# Teensy32.net
KiCad netlist of a schematic drawn in Altium Designer
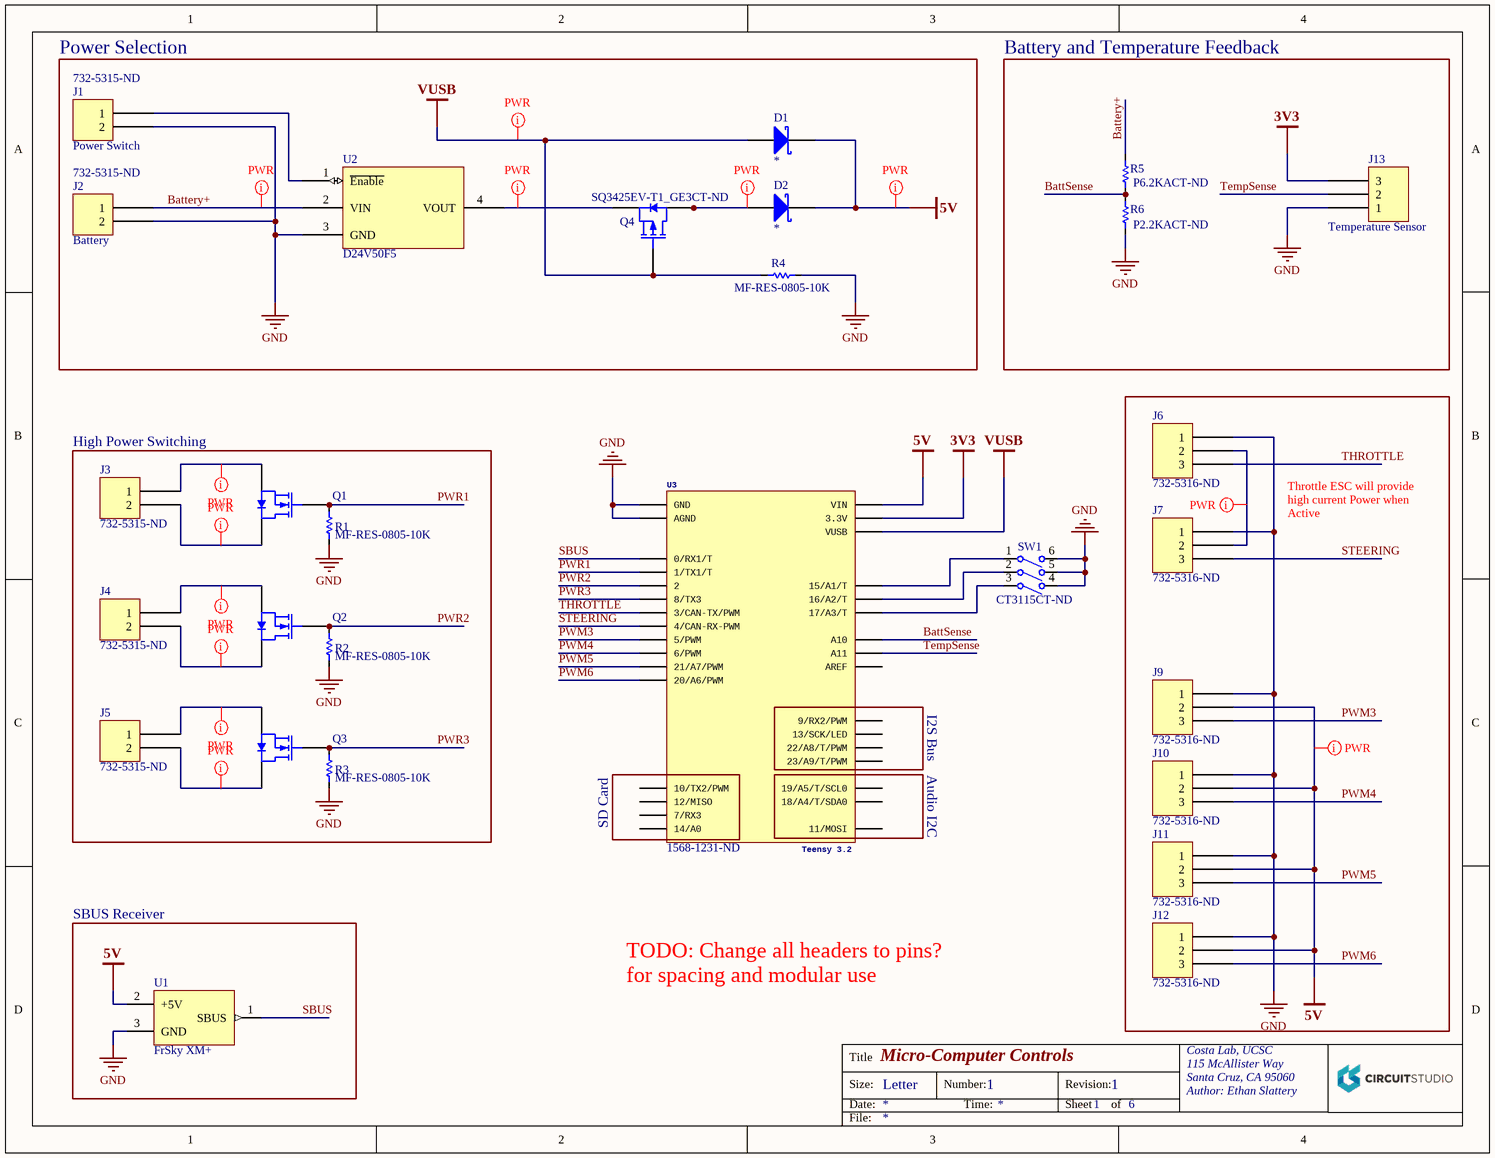
[diagram p0: Teensy32.SchDoc]

(export (version "E")
  (design (tool "Eeschema 10.0.6"))
  (components
    (comp (ref "D1") (value "*") (libsource (lib "DiscreetSemiconductors") (part "Schottky Diode")))
    (comp (ref "D2") (value "*") (libsource (lib "DiscreetSemiconductors") (part "Schottky Diode")))
    (comp (ref "J1")
      (value "Power Switch")
      (footprint "Pinhead_1x2")
      (fields (field (name "SUPPLIER PART NUMBER 1") "732-5315-ND"))
      (libsource (lib "Connectors") (part "2 Pin"))
    )
    (comp (ref "J2")
      (value "Battery")
      (footprint "Pinhead_1x2")
      (fields (field (name "SUPPLIER PART NUMBER 1") "732-5315-ND"))
      (libsource (lib "Connectors") (part "2 Pin"))
    )
    (comp (ref "J3")
      (value "732-5315-ND")
      (footprint "Pinhead_1x2")
      (libsource (lib "Connectors") (part "2 Pin"))
    )
    (comp (ref "J4")
      (value "732-5315-ND")
      (footprint "Pinhead_1x2")
      (libsource (lib "Connectors") (part "2 Pin"))
    )
    (comp (ref "J5")
      (value "732-5315-ND")
      (footprint "Pinhead_1x2")
      (libsource (lib "Connectors") (part "2 Pin"))
    )
    (comp (ref "J6")
      (value "Header")
      (footprint "Pinhead_1x3")
      (fields (field (name "SUPPLIER PART NUMBER 1") "732-5316-ND"))
      (libsource (lib "Connectors") (part "3 Pin"))
    )
    (comp (ref "J7")
      (value "Header")
      (footprint "Pinhead_1x3")
      (fields (field (name "SUPPLIER PART NUMBER 1") "732-5316-ND"))
      (libsource (lib "Connectors") (part "3 Pin"))
    )
    (comp (ref "J9")
      (value "Header")
      (footprint "Pinhead_1x3")
      (fields (field (name "SUPPLIER PART NUMBER 1") "732-5316-ND"))
      (libsource (lib "Connectors") (part "3 Pin"))
    )
    (comp (ref "J10")
      (value "Header")
      (footprint "Pinhead_1x3")
      (fields (field (name "SUPPLIER PART NUMBER 1") "732-5316-ND"))
      (libsource (lib "Connectors") (part "3 Pin"))
    )
    (comp (ref "J11")
      (value "Header")
      (footprint "Pinhead_1x3")
      (fields (field (name "SUPPLIER PART NUMBER 1") "732-5316-ND"))
      (libsource (lib "Connectors") (part "3 Pin"))
    )
    (comp (ref "J12")
      (value "Header")
      (footprint "Pinhead_1x3")
      (fields (field (name "SUPPLIER PART NUMBER 1") "732-5316-ND"))
      (libsource (lib "Connectors") (part "3 Pin"))
    )
    (comp (ref "J13")
      (value "Temperature Sensor")
      (footprint "Pinhead_1x3")
      (libsource (lib "") (part "3 Pin_1"))
    )
    (comp (ref "Q1")
      (value "MOSFET N-Ch")
      (footprint "TO-220")
      (libsource (lib "DiscreetSemiconductors") (part "MOSFET N-Ch"))
    )
    (comp (ref "Q2")
      (value "MOSFET N-Ch")
      (footprint "TO-220")
      (libsource (lib "DiscreetSemiconductors") (part "MOSFET N-Ch"))
    )
    (comp (ref "Q3")
      (value "MOSFET N-Ch")
      (footprint "TO-220")
      (libsource (lib "DiscreetSemiconductors") (part "MOSFET N-Ch"))
    )
    (comp (ref "Q4")
      (value "SQ3425EV-T1_GE3CT-ND")
      (footprint "TSOP-6_L")
      (fields (field (name "HOUSEPART") "NO") (field (name "MPN") "SQ3425EV"))
      (libsource (lib "DiscreetSemiconductors") (part "MOSFET P-CH SOT26 / SOP-6"))
    )
    (comp (ref "R1")
      (value "MF-RES-0805-10K")
      (footprint "R0805N")
      (fields
        (field (name "HOUSEPART") "YES")
        (field (name "TOLERANCE") "5%")
        (field (name "VOLTAGE") "150V")
      )
      (libsource (lib "MF_Passives") (part "RESISTOR"))
    )
    (comp (ref "R2")
      (value "MF-RES-0805-10K")
      (footprint "R0805N")
      (fields
        (field (name "HOUSEPART") "YES")
        (field (name "TOLERANCE") "5%")
        (field (name "VOLTAGE") "150V")
      )
      (libsource (lib "MF_Passives") (part "RESISTOR"))
    )
    (comp (ref "R3")
      (value "MF-RES-0805-10K")
      (footprint "R0805N")
      (fields
        (field (name "HOUSEPART") "YES")
        (field (name "TOLERANCE") "5%")
        (field (name "VOLTAGE") "150V")
      )
      (libsource (lib "MF_Passives") (part "RESISTOR"))
    )
    (comp (ref "R4")
      (value "MF-RES-0805-10K")
      (footprint "R0805N")
      (fields
        (field (name "HOUSEPART") "YES")
        (field (name "TOLERANCE") "5%")
        (field (name "VOLTAGE") "150V")
      )
      (libsource (lib "MF_Passives") (part "RESISTOR"))
    )
    (comp (ref "R5")
      (value "P6.2KACT-ND")
      (footprint "R0805L")
      (libsource (lib "MF_Passives") (part "RESISTOR"))
    )
    (comp (ref "R6")
      (value "P2.2KACT-ND")
      (footprint "R0805L")
      (libsource (lib "MF_Passives") (part "RESISTOR"))
    )
    (comp (ref "SW1")
      (value "CT3115CT-ND")
      (footprint "CTS-219-3")
      (libsource (lib "Switches") (part "SPST 3-position"))
    )
    (comp (ref "U1")
      (value "FrSky XM+")
      (footprint "FrSky XM+ (Vert Mount)")
      (description "FrSky 2.4GHz 16CH SBUS receiver")
      (libsource (lib "BreakoutBoards") (part "FrSky XM+ Radio"))
    )
    (comp (ref "U2")
      (value "D24V50F5")
      (footprint "D24V50Fx")
      (description "DC Step Down Regulators from Pololu")
      (libsource (lib "BreakoutBoards") (part "D24V25Fx"))
    )
    (comp (ref "U3")
      (value "Teensy 3.2")
      (footprint "TEENSY_3.0-3.2&LC_SMD+4")
      (description "Teensy 3.2 /w 4 inner pins")
      (fields (field (name "SUPPLIER PART NUMBER 1") "1568-1231-ND"))
      (libsource (lib "BreakoutBoards") (part "TEENSY 3.2 + 4"))
    )
  )
  (nets
    (net (code "1") (name "/BattSense") (class "Default")
      (node (ref "R5") (pin "1") (pinfunction "1_1") (pintype "passive"))
      (node (ref "R6") (pin "2") (pinfunction "2_2") (pintype "passive"))
      (node (ref "U3") (pin "A10") (pinfunction "A10_A10") (pintype "passive"))
    )
    (net (code "2") (name "/Battery+") (class "Default")
      (node (ref "J2") (pin "1") (pinfunction "1_1") (pintype "passive"))
      (node (ref "R5") (pin "2") (pinfunction "2_2") (pintype "passive"))
      (node (ref "U2") (pin "2") (pinfunction "VIN_2") (pintype "power_in"))
    )
    (net (code "3") (name "/PWM3") (class "Default")
      (node (ref "J9") (pin "3") (pinfunction "3_3") (pintype "passive"))
      (node (ref "U3") (pin "5") (pinfunction "5/PWM_5") (pintype "passive"))
    )
    (net (code "4") (name "/PWM4") (class "Default")
      (node (ref "J10") (pin "3") (pinfunction "3_3") (pintype "passive"))
      (node (ref "U3") (pin "6") (pinfunction "6/PWM_6") (pintype "passive"))
    )
    (net (code "5") (name "/PWM5") (class "Default")
      (node (ref "J11") (pin "3") (pinfunction "3_3") (pintype "passive"))
      (node (ref "U3") (pin "21/A7") (pinfunction "21/A7/PWM_21/A7") (pintype "passive"))
    )
    (net (code "6") (name "/PWM6") (class "Default")
      (node (ref "J12") (pin "3") (pinfunction "3_3") (pintype "passive"))
      (node (ref "U3") (pin "20/A6") (pinfunction "20/A6/PWM_20/A6") (pintype "passive"))
    )
    (net (code "7") (name "/PWR1") (class "Default")
      (node (ref "Q1") (pin "1") (pinfunction "G_1") (pintype "passive"))
      (node (ref "R1") (pin "1") (pinfunction "1_1") (pintype "passive"))
      (node (ref "U3") (pin "1") (pinfunction "1/TX1/T_1") (pintype "passive"))
    )
    (net (code "8") (name "/PWR2") (class "Default")
      (node (ref "Q2") (pin "1") (pinfunction "G_1") (pintype "passive"))
      (node (ref "R2") (pin "1") (pinfunction "1_1") (pintype "passive"))
      (node (ref "U3") (pin "2") (pinfunction "2_2") (pintype "passive"))
    )
    (net (code "9") (name "/PWR3") (class "Default")
      (node (ref "Q3") (pin "1") (pinfunction "G_1") (pintype "passive"))
      (node (ref "R3") (pin "1") (pinfunction "1_1") (pintype "passive"))
      (node (ref "U3") (pin "8") (pinfunction "8/TX3_8") (pintype "passive"))
    )
    (net (code "10") (name "/SBUS") (class "Default")
      (node (ref "U1") (pin "1") (pinfunction "SBUS_1") (pintype "output"))
      (node (ref "U3") (pin "0") (pinfunction "0/RX1/T_0") (pintype "passive"))
    )
    (net (code "11") (name "/STEERING") (class "Default")
      (node (ref "J7") (pin "3") (pinfunction "3_3") (pintype "passive"))
      (node (ref "U3") (pin "4") (pinfunction "4/CAN-RX-PWM_4") (pintype "passive"))
    )
    (net (code "12") (name "/THROTTLE") (class "Default")
      (node (ref "J6") (pin "3") (pinfunction "3_3") (pintype "passive"))
      (node (ref "U3") (pin "3") (pinfunction "3/CAN-TX/PWM_3") (pintype "passive"))
    )
    (net (code "13") (name "/TempSense") (class "Default")
      (node (ref "J13") (pin "2") (pinfunction "2_2") (pintype "passive"))
      (node (ref "U3") (pin "A11") (pinfunction "A11_A11") (pintype "passive"))
    )
    (net (code "14") (name "3V3") (class "Default")
      (node (ref "J13") (pin "3") (pinfunction "3_3") (pintype "passive"))
      (node (ref "U3") (pin "3.3V") (pinfunction "3.3V_3.3V") (pintype "power_in"))
    )
    (net (code "15") (name "5V") (class "Default")
      (node (ref "D1") (pin "2") (pinfunction "K_2") (pintype "passive"))
      (node (ref "D2") (pin "2") (pinfunction "K_2") (pintype "passive"))
      (node (ref "J10") (pin "2") (pinfunction "2_2") (pintype "passive"))
      (node (ref "J11") (pin "2") (pinfunction "2_2") (pintype "passive"))
      (node (ref "J12") (pin "2") (pinfunction "2_2") (pintype "passive"))
      (node (ref "J9") (pin "2") (pinfunction "2_2") (pintype "passive"))
      (node (ref "U1") (pin "2") (pinfunction "+5V_2") (pintype "power_in"))
      (node (ref "U3") (pin "VIN") (pinfunction "VIN_VIN") (pintype "power_in"))
    )
    (net (code "16") (name "GND") (class "Default")
      (node (ref "J1") (pin "2") (pinfunction "2_2") (pintype "passive"))
      (node (ref "J10") (pin "1") (pinfunction "1_1") (pintype "passive"))
      (node (ref "J11") (pin "1") (pinfunction "1_1") (pintype "passive"))
      (node (ref "J12") (pin "1") (pinfunction "1_1") (pintype "passive"))
      (node (ref "J13") (pin "1") (pinfunction "1_1") (pintype "passive"))
      (node (ref "J2") (pin "2") (pinfunction "2_2") (pintype "passive"))
      (node (ref "J6") (pin "1") (pinfunction "1_1") (pintype "passive"))
      (node (ref "J7") (pin "1") (pinfunction "1_1") (pintype "passive"))
      (node (ref "J9") (pin "1") (pinfunction "1_1") (pintype "passive"))
      (node (ref "R1") (pin "2") (pinfunction "2_2") (pintype "passive"))
      (node (ref "R2") (pin "2") (pinfunction "2_2") (pintype "passive"))
      (node (ref "R3") (pin "2") (pinfunction "2_2") (pintype "passive"))
      (node (ref "R4") (pin "2") (pinfunction "2_2") (pintype "passive"))
      (node (ref "R6") (pin "1") (pinfunction "1_1") (pintype "passive"))
      (node (ref "SW1") (pin "4") (pinfunction "B3_4") (pintype "passive"))
      (node (ref "SW1") (pin "5") (pinfunction "B2_5") (pintype "passive"))
      (node (ref "SW1") (pin "6") (pinfunction "B1_6") (pintype "passive"))
      (node (ref "U1") (pin "3") (pinfunction "GND_3") (pintype "power_in"))
      (node (ref "U2") (pin "3") (pinfunction "GND_3") (pintype "power_in"))
      (node (ref "U3") (pin "AGND") (pinfunction "AGND_AGND") (pintype "power_in"))
      (node (ref "U3") (pin "GND") (pinfunction "GND_GND") (pintype "power_in"))
    )
    (net (code "17") (name "Net-(D2-A)") (class "Default")
      (node (ref "D2") (pin "1") (pinfunction "A_1") (pintype "passive"))
      (node (ref "Q4") (pin "1") (pinfunction "D_1") (pintype "passive"))
      (node (ref "Q4") (pin "2") (pinfunction "D_2") (pintype "passive"))
      (node (ref "Q4") (pin "5") (pinfunction "D_5") (pintype "passive"))
      (node (ref "Q4") (pin "6") (pinfunction "D_6") (pintype "passive"))
    )
    (net (code "18") (name "Net-(J6-Pad2)") (class "Default")
      (node (ref "J6") (pin "2") (pinfunction "2_2") (pintype "passive"))
      (node (ref "J7") (pin "2") (pinfunction "2_2") (pintype "passive"))
    )
    (net (code "19") (name "Net-(Q1-D)") (class "Default")
      (node (ref "J3") (pin "2") (pinfunction "2_2") (pintype "passive"))
      (node (ref "Q1") (pin "2") (pinfunction "D_2") (pintype "passive"))
    )
    (net (code "20") (name "Net-(Q1-S)") (class "Default")
      (node (ref "J3") (pin "1") (pinfunction "1_1") (pintype "passive"))
      (node (ref "Q1") (pin "3") (pinfunction "S_3") (pintype "passive"))
    )
    (net (code "21") (name "Net-(Q2-D)") (class "Default")
      (node (ref "J4") (pin "2") (pinfunction "2_2") (pintype "passive"))
      (node (ref "Q2") (pin "2") (pinfunction "D_2") (pintype "passive"))
    )
    (net (code "22") (name "Net-(Q2-S)") (class "Default")
      (node (ref "J4") (pin "1") (pinfunction "1_1") (pintype "passive"))
      (node (ref "Q2") (pin "3") (pinfunction "S_3") (pintype "passive"))
    )
    (net (code "23") (name "Net-(Q3-D)") (class "Default")
      (node (ref "J5") (pin "2") (pinfunction "2_2") (pintype "passive"))
      (node (ref "Q3") (pin "2") (pinfunction "D_2") (pintype "passive"))
    )
    (net (code "24") (name "Net-(Q3-S)") (class "Default")
      (node (ref "J5") (pin "1") (pinfunction "1_1") (pintype "passive"))
      (node (ref "Q3") (pin "3") (pinfunction "S_3") (pintype "passive"))
    )
    (net (code "25") (name "Net-(Q4-S)") (class "Default")
      (node (ref "Q4") (pin "4") (pinfunction "S_4") (pintype "passive"))
      (node (ref "U2") (pin "4") (pinfunction "VOUT_4") (pintype "power_in"))
    )
    (net (code "26") (name "Net-(SW1-A1)") (class "Default")
      (node (ref "SW1") (pin "1") (pinfunction "A1_1") (pintype "passive"))
      (node (ref "U3") (pin "15/A1") (pinfunction "15/A1/T_15/A1") (pintype "passive"))
    )
    (net (code "27") (name "Net-(SW1-A2)") (class "Default")
      (node (ref "SW1") (pin "2") (pinfunction "A2_2") (pintype "passive"))
      (node (ref "U3") (pin "16/A2") (pinfunction "16/A2/T_16/A2") (pintype "passive"))
    )
    (net (code "28") (name "Net-(SW1-A3)") (class "Default")
      (node (ref "SW1") (pin "3") (pinfunction "A3_3") (pintype "passive"))
      (node (ref "U3") (pin "17/A3") (pinfunction "17/A3/T_17/A3") (pintype "passive"))
    )
    (net (code "29") (name "Net-(U2-~{Enable})") (class "Default")
      (node (ref "J1") (pin "1") (pinfunction "1_1") (pintype "passive"))
      (node (ref "U2") (pin "1") (pinfunction "~{Enable}_1") (pintype "bidirectional"))
    )
    (net (code "30") (name "VUSB") (class "Default")
      (node (ref "D1") (pin "1") (pinfunction "A_1") (pintype "passive"))
      (node (ref "Q4") (pin "3") (pinfunction "G_3") (pintype "passive"))
      (node (ref "R4") (pin "1") (pinfunction "1_1") (pintype "passive"))
      (node (ref "U3") (pin "VUSB") (pinfunction "VUSB_VUSB") (pintype "power_in"))
    )
    (net (code "31") (name "unconnected-(U3-7{slash}RX3-Pad7)") (class "Default")
      (node (ref "U3") (pin "7") (pinfunction "7/RX3_7") (pintype "passive"))
    )
    (net (code "32") (name "unconnected-(U3-9{slash}RX2{slash}PWM-Pad9)") (class "Default")
      (node (ref "U3") (pin "9") (pinfunction "9/RX2/PWM_9") (pintype "passive"))
    )
    (net (code "33") (name "unconnected-(U3-10{slash}TX2{slash}PWM-Pad10)") (class "Default")
      (node (ref "U3") (pin "10") (pinfunction "10/TX2/PWM_10") (pintype "passive"))
    )
    (net (code "34") (name "unconnected-(U3-11{slash}MOSI-Pad11)") (class "Default")
      (node (ref "U3") (pin "11") (pinfunction "11/MOSI_11") (pintype "passive"))
    )
    (net (code "35") (name "unconnected-(U3-12{slash}MISO-Pad12)") (class "Default")
      (node (ref "U3") (pin "12") (pinfunction "12/MISO_12") (pintype "passive"))
    )
    (net (code "36") (name "unconnected-(U3-13{slash}SCK{slash}LED-Pad13)") (class "Default")
      (node (ref "U3") (pin "13") (pinfunction "13/SCK/LED_13") (pintype "passive"))
    )
    (net (code "37") (name "unconnected-(U3-18{slash}A4{slash}T{slash}SDA0-Pad18{slash}A4)") (class "Default")
      (node (ref "U3") (pin "18/A4") (pinfunction "18/A4/T/SDA0_18/A4") (pintype "passive"))
    )
    (net (code "38") (name "unconnected-(U3-19{slash}A5{slash}T{slash}SCL0-Pad19{slash}A5)") (class "Default")
      (node (ref "U3") (pin "19/A5") (pinfunction "19/A5/T/SCL0_19/A5") (pintype "passive"))
    )
    (net (code "39") (name "unconnected-(U3-22{slash}A8{slash}T{slash}PWM-Pad22{slash}A8)") (class "Default")
      (node (ref "U3") (pin "22/A8") (pinfunction "22/A8/T/PWM_22/A8") (pintype "passive"))
    )
    (net (code "40") (name "unconnected-(U3-23{slash}A9{slash}T{slash}PWM-Pad23{slash}A9)") (class "Default")
      (node (ref "U3") (pin "23/A9") (pinfunction "23/A9/T/PWM_23/A9") (pintype "passive"))
    )
    (net (code "41") (name "unconnected-(U3-Pad14{slash}A0)") (class "Default")
      (node (ref "U3") (pin "14/A0") (pinfunction "14/A0_14/A0") (pintype "passive"))
    )
    (net (code "42") (name "unconnected-(U3-PadAREF)") (class "Default")
      (node (ref "U3") (pin "AREF") (pinfunction "AREF_AREF") (pintype "power_in"))
    )
  )
)
